# TeslaBMS_Shield.net
KiCad netlist of a schematic drawn in EAGLE
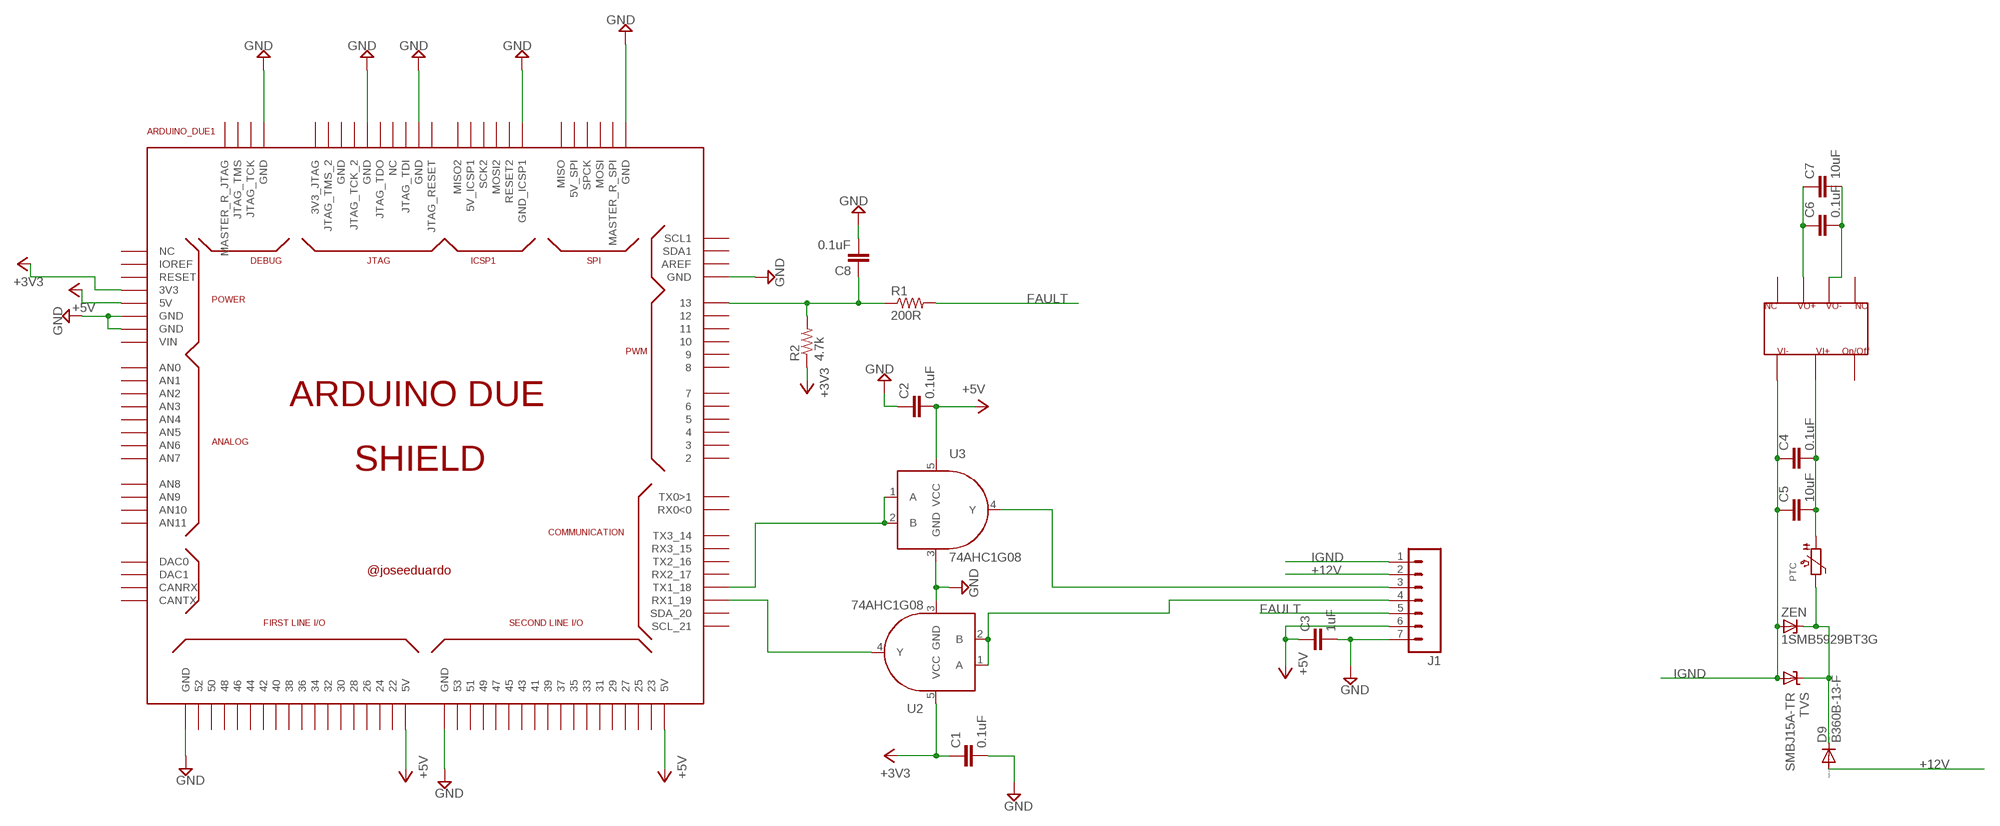
[diagram p0: schematic, sheet 1]

(export (version "E")
  (design (tool "Eeschema 10.0.6"))
  (components
    (comp (ref "ARDUINO_DUE1")
      (value "ARDUINO_DUE_SHIELD")
      (footprint "eagle-import:ARDUINO_DUE_SHIELD")
      (libsource (lib "eagle-import") (part "ARDUINO_DUE_SHIELD"))
    )
    (comp (ref "C1")
      (value "0.1uF")
      (footprint "eagle-import:0603-CAP")
      (libsource (lib "eagle-import") (part "CAP0603-CAP"))
    )
    (comp (ref "C2")
      (value "0.1uF")
      (footprint "eagle-import:0603-CAP")
      (libsource (lib "eagle-import") (part "CAP0603-CAP"))
    )
    (comp (ref "C3")
      (value "1uF")
      (footprint "eagle-import:0603-CAP")
      (libsource (lib "eagle-import") (part "CAP0603-CAP"))
    )
    (comp (ref "C4")
      (value "0.1uF")
      (footprint "eagle-import:0805")
      (libsource (lib "eagle-import") (part "CAP0805"))
    )
    (comp (ref "C5")
      (value "10uF")
      (footprint "eagle-import:0805")
      (libsource (lib "eagle-import") (part "CAP0805"))
    )
    (comp (ref "C6")
      (value "0.1uF")
      (footprint "eagle-import:0805")
      (libsource (lib "eagle-import") (part "CAP0805"))
    )
    (comp (ref "C7")
      (value "10uF")
      (footprint "eagle-import:0805")
      (libsource (lib "eagle-import") (part "CAP0805"))
    )
    (comp (ref "C8")
      (value "0.1uF")
      (footprint "eagle-import:0603-CAP")
      (libsource (lib "eagle-import") (part "CAP0603-CAP"))
    )
    (comp (ref "D9")
      (value "B360B-13-F")
      (footprint "eagle-import:SMB")
      (libsource (lib "eagle-import") (part "DIODE-SMB"))
    )
    (comp (ref "J1")
      (value "M07LONGPADS")
      (footprint "eagle-import:1X07_LONGPADS")
      (libsource (lib "eagle-import") (part "M07LONGPADS"))
    )
    (comp (ref "PTC")
      (value "PTC1812")
      (footprint "eagle-import:PTC1812")
      (libsource (lib "eagle-import") (part "PTC1812"))
    )
    (comp (ref "R1")
      (value "200R")
      (footprint "eagle-import:0603-RES")
      (libsource (lib "eagle-import") (part "RESISTOR0603-RES"))
    )
    (comp (ref "R2")
      (value "4.7k")
      (footprint "eagle-import:0603-RES")
      (libsource (lib "eagle-import") (part "RESISTOR0603-RES"))
    )
    (comp (ref "TVS")
      (value "SMBJ15A-TR")
      (footprint "eagle-import:SMBJ")
      (libsource (lib "eagle-import") (part "SUPPRESSOR-SMBJ"))
    )
    (comp (ref "U1")
      (value "CINCON5V")
      (footprint "eagle-import:CINCON5V")
      (libsource (lib "eagle-import") (part "CINCON5V"))
    )
    (comp (ref "U2")
      (value "74AHC1G08")
      (footprint "eagle-import:SOT353")
      (libsource (lib "eagle-import") (part "74AHC1G08"))
    )
    (comp (ref "U3")
      (value "74AHC1G08")
      (footprint "eagle-import:SOT353")
      (libsource (lib "eagle-import") (part "74AHC1G08"))
    )
    (comp (ref "ZEN")
      (value "1SMB5929BT3G")
      (footprint "eagle-import:SMB")
      (libsource (lib "eagle-import") (part "ZENER-DIODESMB"))
    )
  )
  (nets
    (net (code "1") (name "+3V3") (class "Default")
      (node (ref "ARDUINO_DUE1") (pin "3V3") (pinfunction "3V3_3V3") (pintype "bidirectional"))
      (node (ref "C1") (pin "1") (pinfunction "1_1") (pintype "passive"))
      (node (ref "R2") (pin "1") (pinfunction "1_1") (pintype "passive"))
      (node (ref "U2") (pin "5") (pinfunction "VCC_5") (pintype "bidirectional"))
    )
    (net (code "2") (name "+5V") (class "Default")
      (node (ref "ARDUINO_DUE1") (pin "5V0") (pinfunction "5V_5V0") (pintype "bidirectional"))
      (node (ref "ARDUINO_DUE1") (pin "5V0_1") (pinfunction "5V_5V0_1") (pintype "bidirectional"))
      (node (ref "ARDUINO_DUE1") (pin "5V0_2") (pinfunction "5V_5V0_2") (pintype "bidirectional"))
      (node (ref "C2") (pin "2") (pinfunction "2_2") (pintype "passive"))
      (node (ref "C3") (pin "1") (pinfunction "1_1") (pintype "passive"))
      (node (ref "C6") (pin "1") (pinfunction "1_1") (pintype "passive"))
      (node (ref "C7") (pin "1") (pinfunction "1_1") (pintype "passive"))
      (node (ref "J1") (pin "6") (pinfunction "6_6") (pintype "passive"))
      (node (ref "U1") (pin "P$5") (pinfunction "P$5_P$5") (pintype "bidirectional"))
      (node (ref "U3") (pin "5") (pinfunction "VCC_5") (pintype "bidirectional"))
    )
    (net (code "3") (name "/+12V") (class "Default")
      (node (ref "D9") (pin "A") (pinfunction "A_A") (pintype "passive"))
      (node (ref "J1") (pin "2") (pinfunction "2_2") (pintype "passive"))
    )
    (net (code "4") (name "/FAULT") (class "Default")
      (node (ref "J1") (pin "5") (pinfunction "5_5") (pintype "passive"))
      (node (ref "R1") (pin "2") (pinfunction "2_2") (pintype "passive"))
    )
    (net (code "5") (name "/IGND") (class "Default")
      (node (ref "C4") (pin "1") (pinfunction "1_1") (pintype "passive"))
      (node (ref "C5") (pin "1") (pinfunction "1_1") (pintype "passive"))
      (node (ref "J1") (pin "1") (pinfunction "1_1") (pintype "passive"))
      (node (ref "TVS") (pin "A") (pinfunction "A_A") (pintype "passive"))
      (node (ref "U1") (pin "P$1") (pinfunction "P$1_P$1") (pintype "bidirectional"))
      (node (ref "ZEN") (pin "A") (pinfunction "A_A") (pintype "passive"))
    )
    (net (code "6") (name "GND") (class "Default")
      (node (ref "ARDUINO_DUE1") (pin "GND") (pinfunction "GND_GND") (pintype "bidirectional"))
      (node (ref "ARDUINO_DUE1") (pin "GND_1") (pinfunction "GND_GND_1") (pintype "bidirectional"))
      (node (ref "ARDUINO_DUE1") (pin "GND_10") (pinfunction "GND_GND_10") (pintype "bidirectional"))
      (node (ref "ARDUINO_DUE1") (pin "GND_2") (pinfunction "GND_GND_2") (pintype "bidirectional"))
      (node (ref "ARDUINO_DUE1") (pin "GND_3") (pinfunction "GND_GND_3") (pintype "bidirectional"))
      (node (ref "ARDUINO_DUE1") (pin "GND_4") (pinfunction "GND_GND_4") (pintype "bidirectional"))
      (node (ref "ARDUINO_DUE1") (pin "GND_5") (pinfunction "GND_GND_5") (pintype "bidirectional"))
      (node (ref "ARDUINO_DUE1") (pin "GND_7") (pinfunction "GND_GND_7") (pintype "bidirectional"))
      (node (ref "ARDUINO_DUE1") (pin "GND_9") (pinfunction "GND_GND_9") (pintype "bidirectional"))
      (node (ref "ARDUINO_DUE1") (pin "GND_ICSP1") (pinfunction "GND_ICSP1_GND_ICSP1") (pintype "bidirectional"))
      (node (ref "C1") (pin "2") (pinfunction "2_2") (pintype "passive"))
      (node (ref "C2") (pin "1") (pinfunction "1_1") (pintype "passive"))
      (node (ref "C3") (pin "2") (pinfunction "2_2") (pintype "passive"))
      (node (ref "C6") (pin "2") (pinfunction "2_2") (pintype "passive"))
      (node (ref "C7") (pin "2") (pinfunction "2_2") (pintype "passive"))
      (node (ref "C8") (pin "2") (pinfunction "2_2") (pintype "passive"))
      (node (ref "J1") (pin "7") (pinfunction "7_7") (pintype "passive"))
      (node (ref "U1") (pin "P$6") (pinfunction "P$6_P$6") (pintype "bidirectional"))
      (node (ref "U2") (pin "3") (pinfunction "GND_3") (pintype "bidirectional"))
      (node (ref "U3") (pin "3") (pinfunction "GND_3") (pintype "bidirectional"))
    )
    (net (code "7") (name "Net-(ARDUINO_DUE1-Pad13)") (class "Default")
      (node (ref "ARDUINO_DUE1") (pin "13") (pinfunction "13_13") (pintype "bidirectional"))
      (node (ref "C8") (pin "1") (pinfunction "1_1") (pintype "passive"))
      (node (ref "R1") (pin "1") (pinfunction "1_1") (pintype "passive"))
      (node (ref "R2") (pin "2") (pinfunction "2_2") (pintype "passive"))
    )
    (net (code "8") (name "Net-(ARDUINO_DUE1-RX1_19)") (class "Default")
      (node (ref "ARDUINO_DUE1") (pin "19") (pinfunction "RX1_19_19") (pintype "bidirectional"))
      (node (ref "U2") (pin "4") (pinfunction "Y_4") (pintype "bidirectional"))
    )
    (net (code "9") (name "Net-(ARDUINO_DUE1-TX1_18)") (class "Default")
      (node (ref "ARDUINO_DUE1") (pin "18") (pinfunction "TX1_18_18") (pintype "bidirectional"))
      (node (ref "U3") (pin "1") (pinfunction "A_1") (pintype "bidirectional"))
      (node (ref "U3") (pin "2") (pinfunction "B_2") (pintype "bidirectional"))
    )
    (net (code "10") (name "Net-(PTC-1)") (class "Default")
      (node (ref "C4") (pin "2") (pinfunction "2_2") (pintype "passive"))
      (node (ref "C5") (pin "2") (pinfunction "2_2") (pintype "passive"))
      (node (ref "PTC") (pin "P$1") (pinfunction "1_P$1") (pintype "passive"))
      (node (ref "U1") (pin "P$2") (pinfunction "P$2_P$2") (pintype "bidirectional"))
    )
    (net (code "11") (name "Net-(PTC-2)") (class "Default")
      (node (ref "D9") (pin "C") (pinfunction "C_C") (pintype "passive"))
      (node (ref "PTC") (pin "P$2") (pinfunction "2_P$2") (pintype "passive"))
      (node (ref "TVS") (pin "C") (pinfunction "C_C") (pintype "passive"))
      (node (ref "ZEN") (pin "C") (pinfunction "C_C") (pintype "passive"))
    )
    (net (code "12") (name "Net-(U2-A)") (class "Default")
      (node (ref "J1") (pin "4") (pinfunction "4_4") (pintype "passive"))
      (node (ref "U2") (pin "1") (pinfunction "A_1") (pintype "bidirectional"))
      (node (ref "U2") (pin "2") (pinfunction "B_2") (pintype "bidirectional"))
    )
    (net (code "13") (name "Net-(U3-Y)") (class "Default")
      (node (ref "J1") (pin "3") (pinfunction "3_3") (pintype "passive"))
      (node (ref "U3") (pin "4") (pinfunction "Y_4") (pintype "bidirectional"))
    )
    (net (code "14") (name "unconnected-(ARDUINO_DUE1-5V_SPI-Pad5V_2)") (class "Default")
      (node (ref "ARDUINO_DUE1") (pin "5V_2") (pinfunction "5V_SPI_5V_2") (pintype "bidirectional"))
    )
    (net (code "15") (name "unconnected-(ARDUINO_DUE1-AN0-PadA0)") (class "Default")
      (node (ref "ARDUINO_DUE1") (pin "A0") (pinfunction "AN0_A0") (pintype "bidirectional"))
    )
    (net (code "16") (name "unconnected-(ARDUINO_DUE1-AN1-PadA1)") (class "Default")
      (node (ref "ARDUINO_DUE1") (pin "A1") (pinfunction "AN1_A1") (pintype "bidirectional"))
    )
    (net (code "17") (name "unconnected-(ARDUINO_DUE1-AN2-PadA2)") (class "Default")
      (node (ref "ARDUINO_DUE1") (pin "A2") (pinfunction "AN2_A2") (pintype "bidirectional"))
    )
    (net (code "18") (name "unconnected-(ARDUINO_DUE1-AN3-PadA3)") (class "Default")
      (node (ref "ARDUINO_DUE1") (pin "A3") (pinfunction "AN3_A3") (pintype "bidirectional"))
    )
    (net (code "19") (name "unconnected-(ARDUINO_DUE1-AN4-PadA4)") (class "Default")
      (node (ref "ARDUINO_DUE1") (pin "A4") (pinfunction "AN4_A4") (pintype "bidirectional"))
    )
    (net (code "20") (name "unconnected-(ARDUINO_DUE1-AN5-PadA5)") (class "Default")
      (node (ref "ARDUINO_DUE1") (pin "A5") (pinfunction "AN5_A5") (pintype "bidirectional"))
    )
    (net (code "21") (name "unconnected-(ARDUINO_DUE1-AN6-PadA6)") (class "Default")
      (node (ref "ARDUINO_DUE1") (pin "A6") (pinfunction "AN6_A6") (pintype "bidirectional"))
    )
    (net (code "22") (name "unconnected-(ARDUINO_DUE1-AN7-PadA7)") (class "Default")
      (node (ref "ARDUINO_DUE1") (pin "A7") (pinfunction "AN7_A7") (pintype "bidirectional"))
    )
    (net (code "23") (name "unconnected-(ARDUINO_DUE1-AN8-PadA8)") (class "Default")
      (node (ref "ARDUINO_DUE1") (pin "A8") (pinfunction "AN8_A8") (pintype "bidirectional"))
    )
    (net (code "24") (name "unconnected-(ARDUINO_DUE1-AN9-PadA9)") (class "Default")
      (node (ref "ARDUINO_DUE1") (pin "A9") (pinfunction "AN9_A9") (pintype "bidirectional"))
    )
    (net (code "25") (name "unconnected-(ARDUINO_DUE1-AN10-PadA10)") (class "Default")
      (node (ref "ARDUINO_DUE1") (pin "A10") (pinfunction "AN10_A10") (pintype "bidirectional"))
    )
    (net (code "26") (name "unconnected-(ARDUINO_DUE1-AN11-PadA11)") (class "Default")
      (node (ref "ARDUINO_DUE1") (pin "A11") (pinfunction "AN11_A11") (pintype "bidirectional"))
    )
    (net (code "27") (name "unconnected-(ARDUINO_DUE1-GND-PadGND_8)") (class "Default")
      (node (ref "ARDUINO_DUE1") (pin "GND_8") (pinfunction "GND_GND_8") (pintype "bidirectional"))
    )
    (net (code "28") (name "unconnected-(ARDUINO_DUE1-MASTER_R_JTAG-PadMASTER_RESET_JTAG)") (class "Default")
      (node (ref "ARDUINO_DUE1") (pin "MASTER_RESET_JTAG") (pinfunction "MASTER_R_JTAG_MASTER_RESET_JTAG") (pintype "bidirectional"))
    )
    (net (code "29") (name "unconnected-(ARDUINO_DUE1-MASTER_R_SPI-PadMASTER_RESET_SPI)") (class "Default")
      (node (ref "ARDUINO_DUE1") (pin "MASTER_RESET_SPI") (pinfunction "MASTER_R_SPI_MASTER_RESET_SPI") (pintype "bidirectional"))
    )
    (net (code "30") (name "unconnected-(ARDUINO_DUE1-NC-PadNC_2)") (class "Default")
      (node (ref "ARDUINO_DUE1") (pin "NC_2") (pinfunction "NC_NC_2") (pintype "no_connect"))
    )
    (net (code "31") (name "unconnected-(ARDUINO_DUE1-NC-PadNC_5)") (class "Default")
      (node (ref "ARDUINO_DUE1") (pin "NC_5") (pinfunction "NC_NC_5") (pintype "bidirectional"))
    )
    (net (code "32") (name "unconnected-(ARDUINO_DUE1-Pad2)") (class "Default")
      (node (ref "ARDUINO_DUE1") (pin "2") (pinfunction "2_2") (pintype "bidirectional"))
    )
    (net (code "33") (name "unconnected-(ARDUINO_DUE1-Pad3)") (class "Default")
      (node (ref "ARDUINO_DUE1") (pin "3") (pinfunction "3_3") (pintype "bidirectional"))
    )
    (net (code "34") (name "unconnected-(ARDUINO_DUE1-Pad3V3_JTAG)") (class "Default")
      (node (ref "ARDUINO_DUE1") (pin "3V3_JTAG") (pinfunction "3V3_JTAG_3V3_JTAG") (pintype "bidirectional"))
    )
    (net (code "35") (name "unconnected-(ARDUINO_DUE1-Pad4)") (class "Default")
      (node (ref "ARDUINO_DUE1") (pin "4") (pinfunction "4_4") (pintype "bidirectional"))
    )
    (net (code "36") (name "unconnected-(ARDUINO_DUE1-Pad5)") (class "Default")
      (node (ref "ARDUINO_DUE1") (pin "5") (pinfunction "5_5") (pintype "bidirectional"))
    )
    (net (code "37") (name "unconnected-(ARDUINO_DUE1-Pad5V_ICSP1)") (class "Default")
      (node (ref "ARDUINO_DUE1") (pin "5V_ICSP1") (pinfunction "5V_ICSP1_5V_ICSP1") (pintype "bidirectional"))
    )
    (net (code "38") (name "unconnected-(ARDUINO_DUE1-Pad6)") (class "Default")
      (node (ref "ARDUINO_DUE1") (pin "6") (pinfunction "6_6") (pintype "bidirectional"))
    )
    (net (code "39") (name "unconnected-(ARDUINO_DUE1-Pad7)") (class "Default")
      (node (ref "ARDUINO_DUE1") (pin "7") (pinfunction "7_7") (pintype "bidirectional"))
    )
    (net (code "40") (name "unconnected-(ARDUINO_DUE1-Pad8)") (class "Default")
      (node (ref "ARDUINO_DUE1") (pin "8") (pinfunction "8_8") (pintype "bidirectional"))
    )
    (net (code "41") (name "unconnected-(ARDUINO_DUE1-Pad9)") (class "Default")
      (node (ref "ARDUINO_DUE1") (pin "9") (pinfunction "9_9") (pintype "bidirectional"))
    )
    (net (code "42") (name "unconnected-(ARDUINO_DUE1-Pad10)") (class "Default")
      (node (ref "ARDUINO_DUE1") (pin "10") (pinfunction "10_10") (pintype "bidirectional"))
    )
    (net (code "43") (name "unconnected-(ARDUINO_DUE1-Pad11)") (class "Default")
      (node (ref "ARDUINO_DUE1") (pin "11") (pinfunction "11_11") (pintype "bidirectional"))
    )
    (net (code "44") (name "unconnected-(ARDUINO_DUE1-Pad12)") (class "Default")
      (node (ref "ARDUINO_DUE1") (pin "12") (pinfunction "12_12") (pintype "bidirectional"))
    )
    (net (code "45") (name "unconnected-(ARDUINO_DUE1-Pad22)") (class "Default")
      (node (ref "ARDUINO_DUE1") (pin "22") (pinfunction "22_22") (pintype "bidirectional"))
    )
    (net (code "46") (name "unconnected-(ARDUINO_DUE1-Pad23)") (class "Default")
      (node (ref "ARDUINO_DUE1") (pin "23") (pinfunction "23_23") (pintype "bidirectional"))
    )
    (net (code "47") (name "unconnected-(ARDUINO_DUE1-Pad24)") (class "Default")
      (node (ref "ARDUINO_DUE1") (pin "24") (pinfunction "24_24") (pintype "bidirectional"))
    )
    (net (code "48") (name "unconnected-(ARDUINO_DUE1-Pad25)") (class "Default")
      (node (ref "ARDUINO_DUE1") (pin "25") (pinfunction "25_25") (pintype "bidirectional"))
    )
    (net (code "49") (name "unconnected-(ARDUINO_DUE1-Pad26)") (class "Default")
      (node (ref "ARDUINO_DUE1") (pin "26") (pinfunction "26_26") (pintype "bidirectional"))
    )
    (net (code "50") (name "unconnected-(ARDUINO_DUE1-Pad27)") (class "Default")
      (node (ref "ARDUINO_DUE1") (pin "27") (pinfunction "27_27") (pintype "bidirectional"))
    )
    (net (code "51") (name "unconnected-(ARDUINO_DUE1-Pad28)") (class "Default")
      (node (ref "ARDUINO_DUE1") (pin "28") (pinfunction "28_28") (pintype "bidirectional"))
    )
    (net (code "52") (name "unconnected-(ARDUINO_DUE1-Pad29)") (class "Default")
      (node (ref "ARDUINO_DUE1") (pin "29") (pinfunction "29_29") (pintype "bidirectional"))
    )
    (net (code "53") (name "unconnected-(ARDUINO_DUE1-Pad30)") (class "Default")
      (node (ref "ARDUINO_DUE1") (pin "30") (pinfunction "30_30") (pintype "bidirectional"))
    )
    (net (code "54") (name "unconnected-(ARDUINO_DUE1-Pad31)") (class "Default")
      (node (ref "ARDUINO_DUE1") (pin "31") (pinfunction "31_31") (pintype "bidirectional"))
    )
    (net (code "55") (name "unconnected-(ARDUINO_DUE1-Pad32)") (class "Default")
      (node (ref "ARDUINO_DUE1") (pin "32") (pinfunction "32_32") (pintype "bidirectional"))
    )
    (net (code "56") (name "unconnected-(ARDUINO_DUE1-Pad33)") (class "Default")
      (node (ref "ARDUINO_DUE1") (pin "33") (pinfunction "33_33") (pintype "bidirectional"))
    )
    (net (code "57") (name "unconnected-(ARDUINO_DUE1-Pad34)") (class "Default")
      (node (ref "ARDUINO_DUE1") (pin "34") (pinfunction "34_34") (pintype "bidirectional"))
    )
    (net (code "58") (name "unconnected-(ARDUINO_DUE1-Pad35)") (class "Default")
      (node (ref "ARDUINO_DUE1") (pin "35") (pinfunction "35_35") (pintype "bidirectional"))
    )
    (net (code "59") (name "unconnected-(ARDUINO_DUE1-Pad36)") (class "Default")
      (node (ref "ARDUINO_DUE1") (pin "36") (pinfunction "36_36") (pintype "bidirectional"))
    )
    (net (code "60") (name "unconnected-(ARDUINO_DUE1-Pad37)") (class "Default")
      (node (ref "ARDUINO_DUE1") (pin "37") (pinfunction "37_37") (pintype "bidirectional"))
    )
    (net (code "61") (name "unconnected-(ARDUINO_DUE1-Pad38)") (class "Default")
      (node (ref "ARDUINO_DUE1") (pin "38") (pinfunction "38_38") (pintype "bidirectional"))
    )
    (net (code "62") (name "unconnected-(ARDUINO_DUE1-Pad39)") (class "Default")
      (node (ref "ARDUINO_DUE1") (pin "39") (pinfunction "39_39") (pintype "bidirectional"))
    )
    (net (code "63") (name "unconnected-(ARDUINO_DUE1-Pad40)") (class "Default")
      (node (ref "ARDUINO_DUE1") (pin "40") (pinfunction "40_40") (pintype "bidirectional"))
    )
    (net (code "64") (name "unconnected-(ARDUINO_DUE1-Pad41)") (class "Default")
      (node (ref "ARDUINO_DUE1") (pin "41") (pinfunction "41_41") (pintype "bidirectional"))
    )
    (net (code "65") (name "unconnected-(ARDUINO_DUE1-Pad42)") (class "Default")
      (node (ref "ARDUINO_DUE1") (pin "42") (pinfunction "42_42") (pintype "bidirectional"))
    )
    (net (code "66") (name "unconnected-(ARDUINO_DUE1-Pad43)") (class "Default")
      (node (ref "ARDUINO_DUE1") (pin "43") (pinfunction "43_43") (pintype "bidirectional"))
    )
    (net (code "67") (name "unconnected-(ARDUINO_DUE1-Pad44)") (class "Default")
      (node (ref "ARDUINO_DUE1") (pin "44") (pinfunction "44_44") (pintype "bidirectional"))
    )
    (net (code "68") (name "unconnected-(ARDUINO_DUE1-Pad45)") (class "Default")
      (node (ref "ARDUINO_DUE1") (pin "45") (pinfunction "45_45") (pintype "bidirectional"))
    )
    (net (code "69") (name "unconnected-(ARDUINO_DUE1-Pad46)") (class "Default")
      (node (ref "ARDUINO_DUE1") (pin "46") (pinfunction "46_46") (pintype "bidirectional"))
    )
    (net (code "70") (name "unconnected-(ARDUINO_DUE1-Pad47)") (class "Default")
      (node (ref "ARDUINO_DUE1") (pin "47") (pinfunction "47_47") (pintype "bidirectional"))
    )
    (net (code "71") (name "unconnected-(ARDUINO_DUE1-Pad48)") (class "Default")
      (node (ref "ARDUINO_DUE1") (pin "48") (pinfunction "48_48") (pintype "bidirectional"))
    )
    (net (code "72") (name "unconnected-(ARDUINO_DUE1-Pad49)") (class "Default")
      (node (ref "ARDUINO_DUE1") (pin "49") (pinfunction "49_49") (pintype "bidirectional"))
    )
    (net (code "73") (name "unconnected-(ARDUINO_DUE1-Pad50)") (class "Default")
      (node (ref "ARDUINO_DUE1") (pin "50") (pinfunction "50_50") (pintype "bidirectional"))
    )
    (net (code "74") (name "unconnected-(ARDUINO_DUE1-Pad51)") (class "Default")
      (node (ref "ARDUINO_DUE1") (pin "51") (pinfunction "51_51") (pintype "bidirectional"))
    )
    (net (code "75") (name "unconnected-(ARDUINO_DUE1-Pad52)") (class "Default")
      (node (ref "ARDUINO_DUE1") (pin "52") (pinfunction "52_52") (pintype "bidirectional"))
    )
    (net (code "76") (name "unconnected-(ARDUINO_DUE1-Pad53)") (class "Default")
      (node (ref "ARDUINO_DUE1") (pin "53") (pinfunction "53_53") (pintype "bidirectional"))
    )
    (net (code "77") (name "unconnected-(ARDUINO_DUE1-PadAREF)") (class "Default")
      (node (ref "ARDUINO_DUE1") (pin "AREF") (pinfunction "AREF_AREF") (pintype "bidirectional"))
    )
    (net (code "78") (name "unconnected-(ARDUINO_DUE1-PadCANRX)") (class "Default")
      (node (ref "ARDUINO_DUE1") (pin "CANRX") (pinfunction "CANRX_CANRX") (pintype "bidirectional"))
    )
    (net (code "79") (name "unconnected-(ARDUINO_DUE1-PadCANTX)") (class "Default")
      (node (ref "ARDUINO_DUE1") (pin "CANTX") (pinfunction "CANTX_CANTX") (pintype "bidirectional"))
    )
    (net (code "80") (name "unconnected-(ARDUINO_DUE1-PadDAC0)") (class "Default")
      (node (ref "ARDUINO_DUE1") (pin "DAC0") (pinfunction "DAC0_DAC0") (pintype "bidirectional"))
    )
    (net (code "81") (name "unconnected-(ARDUINO_DUE1-PadDAC1)") (class "Default")
      (node (ref "ARDUINO_DUE1") (pin "DAC1") (pinfunction "DAC1_DAC1") (pintype "bidirectional"))
    )
    (net (code "82") (name "unconnected-(ARDUINO_DUE1-PadIOREF)") (class "Default")
      (node (ref "ARDUINO_DUE1") (pin "IOREF") (pinfunction "IOREF_IOREF") (pintype "bidirectional"))
    )
    (net (code "83") (name "unconnected-(ARDUINO_DUE1-PadJTAG_RESET)") (class "Default")
      (node (ref "ARDUINO_DUE1") (pin "JTAG_RESET") (pinfunction "JTAG_RESET_JTAG_RESET") (pintype "bidirectional"))
    )
    (net (code "84") (name "unconnected-(ARDUINO_DUE1-PadJTAG_TCK)") (class "Default")
      (node (ref "ARDUINO_DUE1") (pin "JTAG_TCK") (pinfunction "JTAG_TCK_JTAG_TCK") (pintype "bidirectional"))
    )
    (net (code "85") (name "unconnected-(ARDUINO_DUE1-PadJTAG_TCK_2)") (class "Default")
      (node (ref "ARDUINO_DUE1") (pin "JTAG_TCK_2") (pinfunction "JTAG_TCK_2_JTAG_TCK_2") (pintype "bidirectional"))
    )
    (net (code "86") (name "unconnected-(ARDUINO_DUE1-PadJTAG_TDI)") (class "Default")
      (node (ref "ARDUINO_DUE1") (pin "JTAG_TDI") (pinfunction "JTAG_TDI_JTAG_TDI") (pintype "bidirectional"))
    )
    (net (code "87") (name "unconnected-(ARDUINO_DUE1-PadJTAG_TDO)") (class "Default")
      (node (ref "ARDUINO_DUE1") (pin "JTAG_TDO") (pinfunction "JTAG_TDO_JTAG_TDO") (pintype "bidirectional"))
    )
    (net (code "88") (name "unconnected-(ARDUINO_DUE1-PadJTAG_TMS)") (class "Default")
      (node (ref "ARDUINO_DUE1") (pin "JTAG_TMS") (pinfunction "JTAG_TMS_JTAG_TMS") (pintype "bidirectional"))
    )
    (net (code "89") (name "unconnected-(ARDUINO_DUE1-PadJTAG_TMS_2)") (class "Default")
      (node (ref "ARDUINO_DUE1") (pin "JTAG_TMS_2") (pinfunction "JTAG_TMS_2_JTAG_TMS_2") (pintype "bidirectional"))
    )
    (net (code "90") (name "unconnected-(ARDUINO_DUE1-PadMISO)") (class "Default")
      (node (ref "ARDUINO_DUE1") (pin "MISO") (pinfunction "MISO_MISO") (pintype "bidirectional"))
    )
    (net (code "91") (name "unconnected-(ARDUINO_DUE1-PadMISO2)") (class "Default")
      (node (ref "ARDUINO_DUE1") (pin "MISO2") (pinfunction "MISO2_MISO2") (pintype "bidirectional"))
    )
    (net (code "92") (name "unconnected-(ARDUINO_DUE1-PadMOSI)") (class "Default")
      (node (ref "ARDUINO_DUE1") (pin "MOSI") (pinfunction "MOSI_MOSI") (pintype "bidirectional"))
    )
    (net (code "93") (name "unconnected-(ARDUINO_DUE1-PadMOSI2)") (class "Default")
      (node (ref "ARDUINO_DUE1") (pin "MOSI2") (pinfunction "MOSI2_MOSI2") (pintype "bidirectional"))
    )
    (net (code "94") (name "unconnected-(ARDUINO_DUE1-PadRESET)") (class "Default")
      (node (ref "ARDUINO_DUE1") (pin "RESET") (pinfunction "RESET_RESET") (pintype "bidirectional"))
    )
    (net (code "95") (name "unconnected-(ARDUINO_DUE1-PadRESET2)") (class "Default")
      (node (ref "ARDUINO_DUE1") (pin "RESET2") (pinfunction "RESET2_RESET2") (pintype "bidirectional"))
    )
    (net (code "96") (name "unconnected-(ARDUINO_DUE1-PadSCK2)") (class "Default")
      (node (ref "ARDUINO_DUE1") (pin "SCK2") (pinfunction "SCK2_SCK2") (pintype "bidirectional"))
    )
    (net (code "97") (name "unconnected-(ARDUINO_DUE1-PadSCL1)") (class "Default")
      (node (ref "ARDUINO_DUE1") (pin "SCL1") (pinfunction "SCL1_SCL1") (pintype "bidirectional"))
    )
    (net (code "98") (name "unconnected-(ARDUINO_DUE1-PadSDA1)") (class "Default")
      (node (ref "ARDUINO_DUE1") (pin "SDA1") (pinfunction "SDA1_SDA1") (pintype "bidirectional"))
    )
    (net (code "99") (name "unconnected-(ARDUINO_DUE1-PadSPCK)") (class "Default")
      (node (ref "ARDUINO_DUE1") (pin "SPCK") (pinfunction "SPCK_SPCK") (pintype "bidirectional"))
    )
    (net (code "100") (name "unconnected-(ARDUINO_DUE1-PadVIN)") (class "Default")
      (node (ref "ARDUINO_DUE1") (pin "VIN") (pinfunction "VIN_VIN") (pintype "bidirectional"))
    )
    (net (code "101") (name "unconnected-(ARDUINO_DUE1-RX0<0-Pad0)") (class "Default")
      (node (ref "ARDUINO_DUE1") (pin "0") (pinfunction "RX0<0_0") (pintype "bidirectional"))
    )
    (net (code "102") (name "unconnected-(ARDUINO_DUE1-RX2_17-Pad17)") (class "Default")
      (node (ref "ARDUINO_DUE1") (pin "17") (pinfunction "RX2_17_17") (pintype "bidirectional"))
    )
    (net (code "103") (name "unconnected-(ARDUINO_DUE1-RX3_15-Pad15)") (class "Default")
      (node (ref "ARDUINO_DUE1") (pin "15") (pinfunction "RX3_15_15") (pintype "bidirectional"))
    )
    (net (code "104") (name "unconnected-(ARDUINO_DUE1-SCL_21-Pad21)") (class "Default")
      (node (ref "ARDUINO_DUE1") (pin "21") (pinfunction "SCL_21_21") (pintype "bidirectional"))
    )
    (net (code "105") (name "unconnected-(ARDUINO_DUE1-SDA_20-Pad20)") (class "Default")
      (node (ref "ARDUINO_DUE1") (pin "20") (pinfunction "SDA_20_20") (pintype "bidirectional"))
    )
    (net (code "106") (name "unconnected-(ARDUINO_DUE1-TX0>1-Pad1)") (class "Default")
      (node (ref "ARDUINO_DUE1") (pin "1") (pinfunction "TX0>1_1") (pintype "bidirectional"))
    )
    (net (code "107") (name "unconnected-(ARDUINO_DUE1-TX2_16-Pad16)") (class "Default")
      (node (ref "ARDUINO_DUE1") (pin "16") (pinfunction "TX2_16_16") (pintype "bidirectional"))
    )
    (net (code "108") (name "unconnected-(ARDUINO_DUE1-TX3_14-Pad14)") (class "Default")
      (node (ref "ARDUINO_DUE1") (pin "14") (pinfunction "TX3_14_14") (pintype "bidirectional"))
    )
    (net (code "109") (name "unconnected-(U1-PadP$3)") (class "Default")
      (node (ref "U1") (pin "P$3") (pinfunction "P$3_P$3") (pintype "bidirectional"))
    )
    (net (code "110") (name "unconnected-(U1-PadP$4)") (class "Default")
      (node (ref "U1") (pin "P$4") (pinfunction "P$4_P$4") (pintype "bidirectional"))
    )
    (net (code "111") (name "unconnected-(U1-PadP$7)") (class "Default")
      (node (ref "U1") (pin "P$7") (pinfunction "P$7_P$7") (pintype "bidirectional"))
    )
  )
)
